# MCB-Wise-1510-v2_0_0.net
KiCad netlist of a schematic drawn in EAGLE
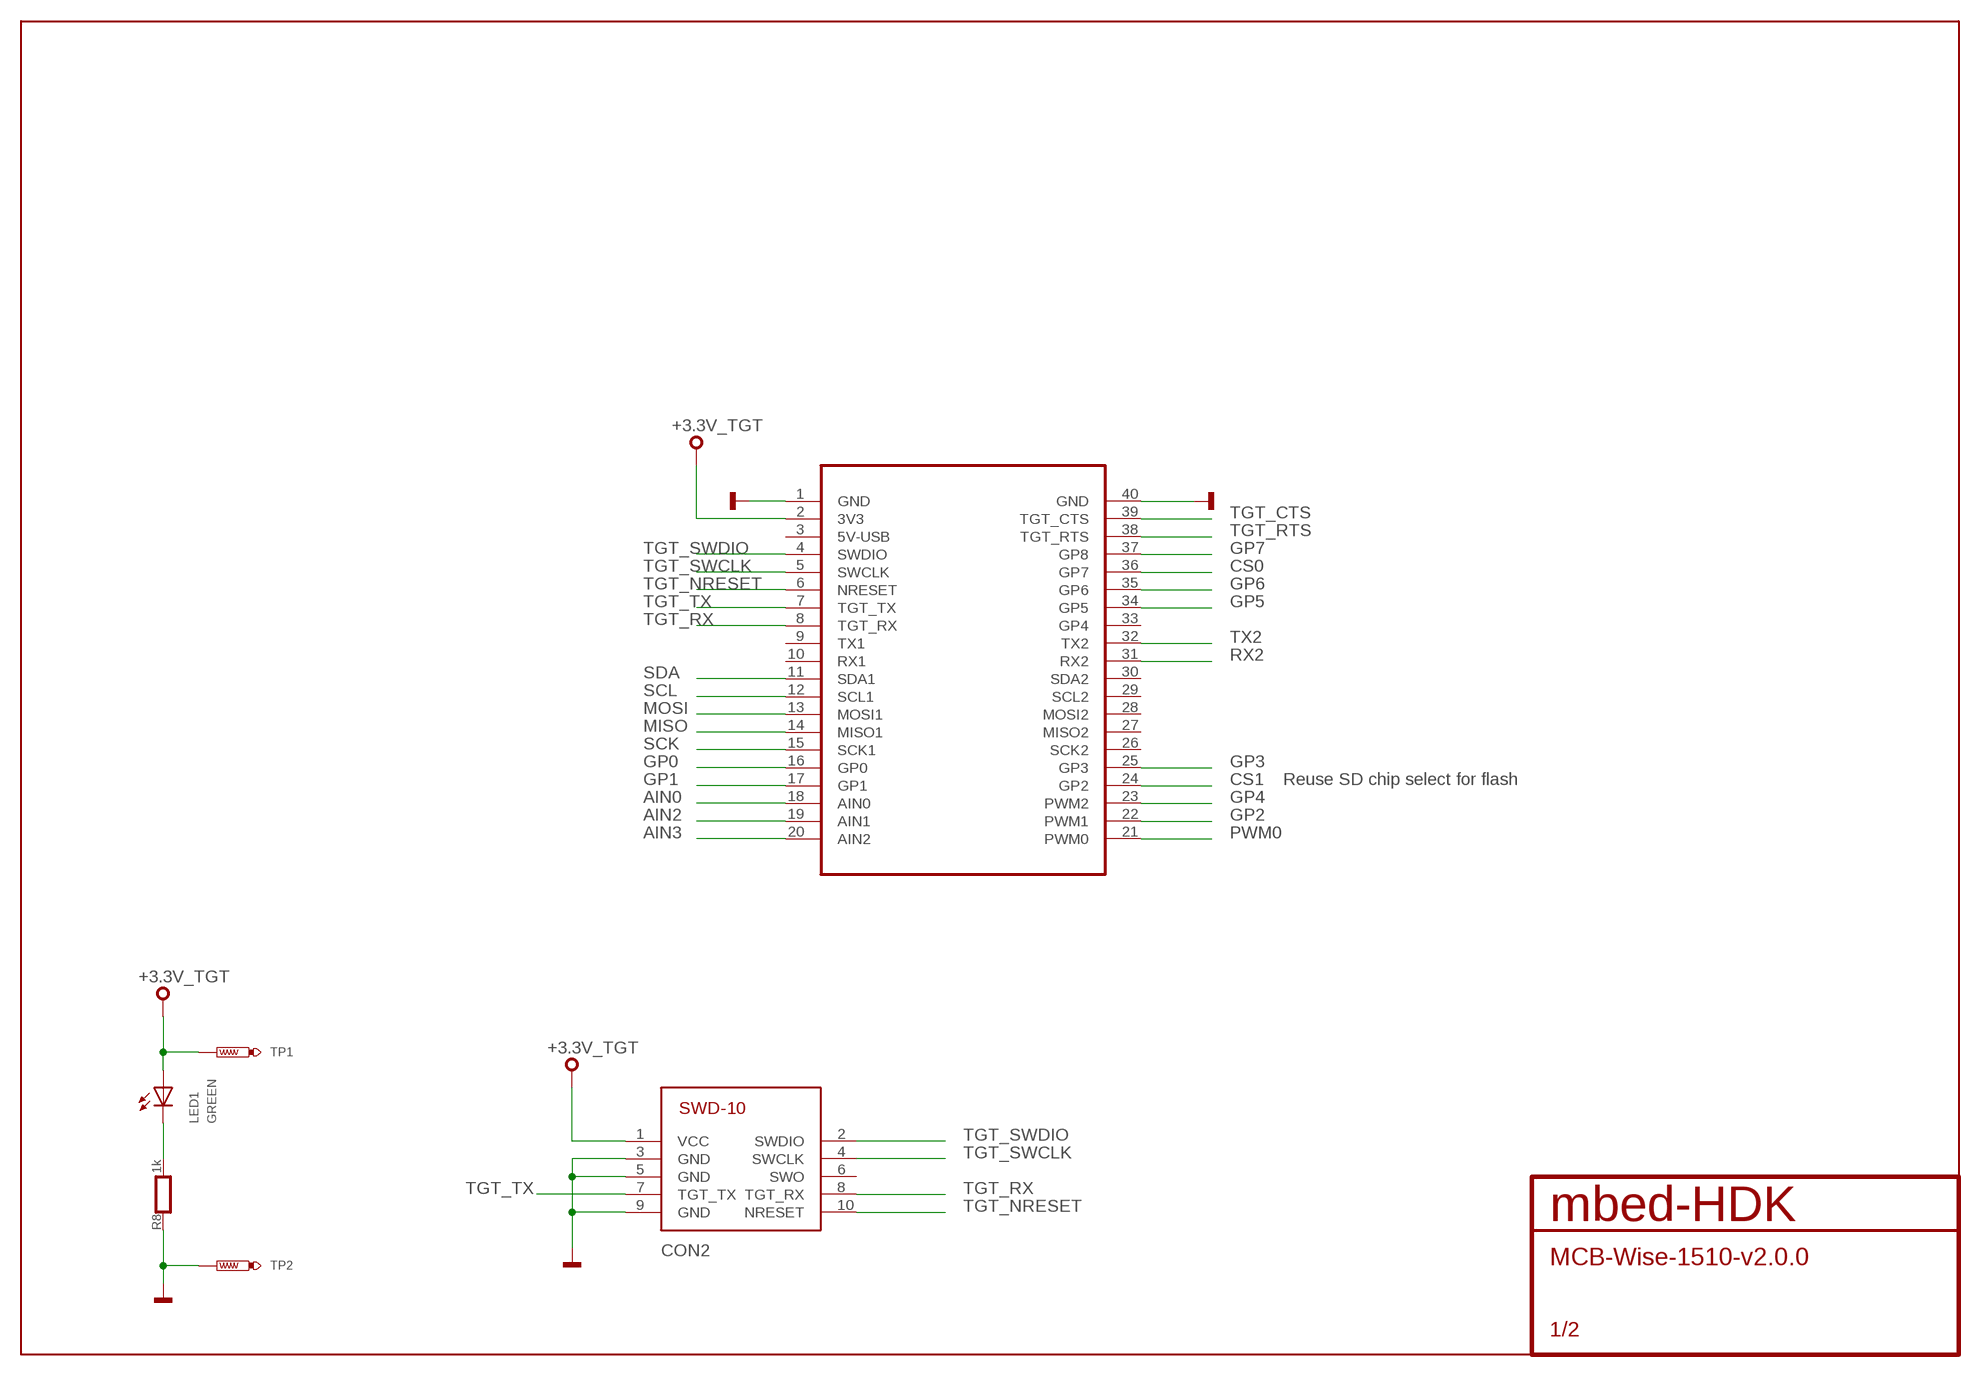
[diagram p0: schematic, sheet 1]
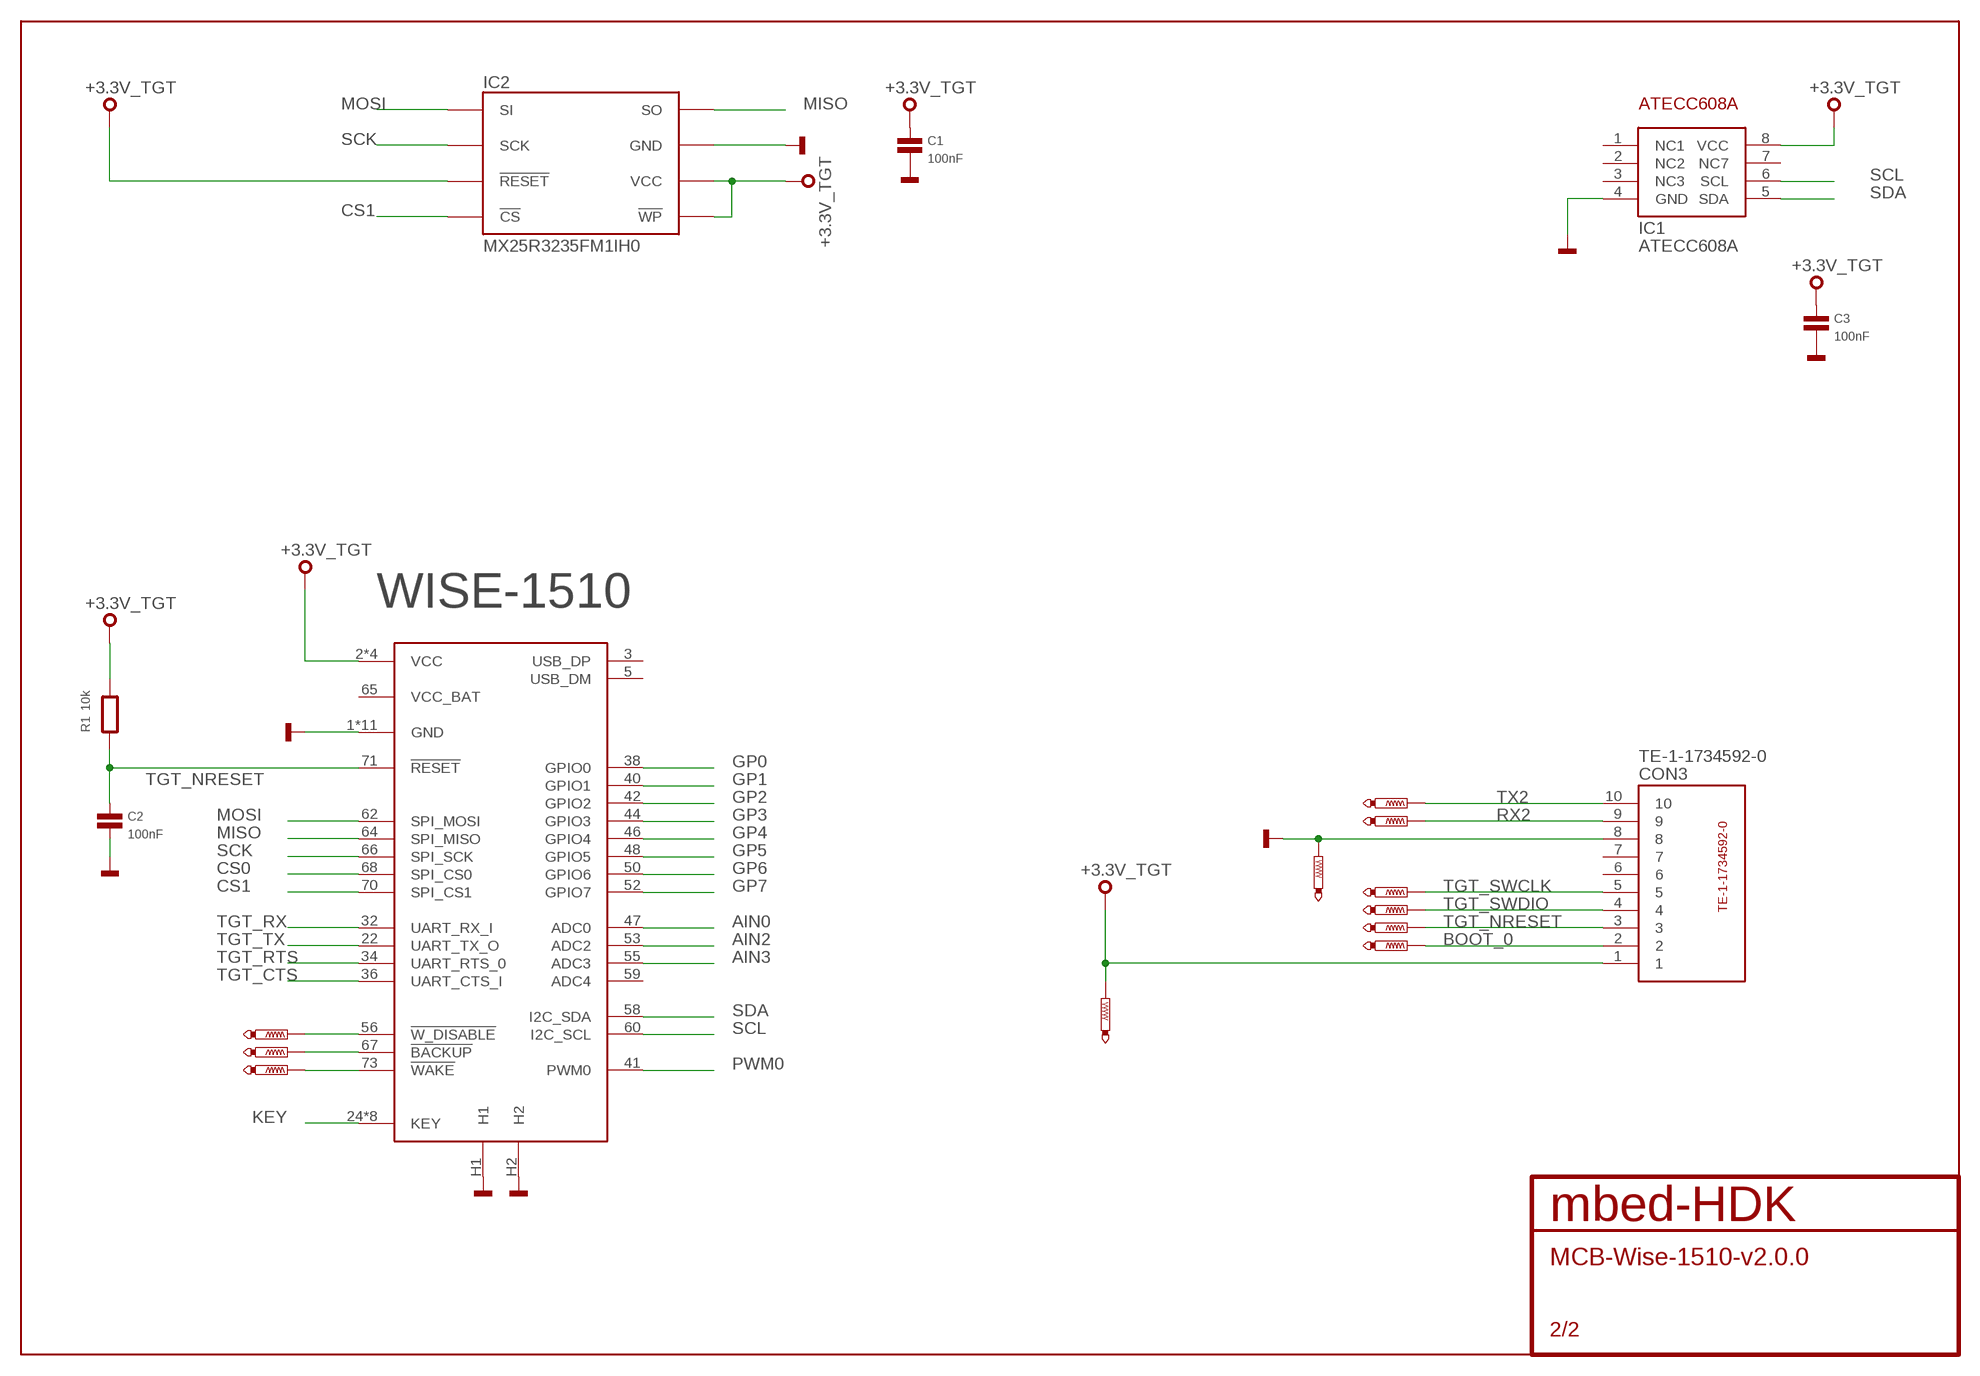
[diagram p1: schematic, sheet 2]

(export (version "E")
  (design (tool "Eeschema 10.0.6"))
  (components
    (comp (ref "C1")
      (value "100nF")
      (footprint "eagle-import:0603")
      (libsource (lib "eagle-import") (part "CAPACITOR0603"))
    )
    (comp (ref "C2")
      (value "100nF")
      (footprint "eagle-import:0603")
      (libsource (lib "eagle-import") (part "CAPACITOR0603"))
    )
    (comp (ref "C3")
      (value "100nF")
      (footprint "eagle-import:0603")
      (libsource (lib "eagle-import") (part "CAPACITOR0603"))
    )
    (comp (ref "CON1")
      (value "WISE-1510_E")
      (footprint "eagle-import:MDT420E02001")
      (libsource (lib "eagle-import") (part "WISE-1510_E"))
    )
    (comp (ref "CON3")
      (value "TE-1-1734592-0")
      (footprint "eagle-import:TE-1-1734592-0")
      (libsource (lib "eagle-import") (part "TE-1-1734592-0"))
    )
    (comp (ref "IC1")
      (value "ATECC608A")
      (footprint "eagle-import:SO8")
      (libsource (lib "eagle-import") (part "ATECC608A"))
    )
    (comp (ref "IC2")
      (value "MX25R3235FM1IH0")
      (footprint "eagle-import:SO8")
      (fields (field (name "MF") "Macronix"))
      (libsource (lib "eagle-import") (part "MX25R3235FM1IH0"))
    )
    (comp (ref "R1")
      (value "10k")
      (footprint "eagle-import:0603")
      (libsource (lib "eagle-import") (part "RESISTOR0603"))
    )
    (comp (ref "TP3")
      (value "PTR1TP08R")
      (footprint "eagle-import:TP08R")
      (libsource (lib "eagle-import") (part "PTR1TP08R"))
    )
    (comp (ref "TP4")
      (value "PTR1TP08R")
      (footprint "eagle-import:TP08R")
      (libsource (lib "eagle-import") (part "PTR1TP08R"))
    )
    (comp (ref "TP5")
      (value "PTR1TP08R")
      (footprint "eagle-import:TP08R")
      (libsource (lib "eagle-import") (part "PTR1TP08R"))
    )
    (comp (ref "TP6")
      (value "PTR1TP08R")
      (footprint "eagle-import:TP08R")
      (libsource (lib "eagle-import") (part "PTR1TP08R"))
    )
    (comp (ref "TP7")
      (value "PTR1TP08R")
      (footprint "eagle-import:TP08R")
      (libsource (lib "eagle-import") (part "PTR1TP08R"))
    )
    (comp (ref "TP8")
      (value "PTR1TP08R")
      (footprint "eagle-import:TP08R")
      (libsource (lib "eagle-import") (part "PTR1TP08R"))
    )
    (comp (ref "TP9")
      (value "PTR1B1,27")
      (footprint "eagle-import:B1,27")
      (libsource (lib "eagle-import") (part "PTR1B1,27"))
    )
    (comp (ref "TP10")
      (value "PTR1B1,27")
      (footprint "eagle-import:B1,27")
      (libsource (lib "eagle-import") (part "PTR1B1,27"))
    )
    (comp (ref "TP11")
      (value "PTR1B1,27")
      (footprint "eagle-import:B1,27")
      (libsource (lib "eagle-import") (part "PTR1B1,27"))
    )
    (comp (ref "TP12")
      (value "PTR1TP08R")
      (footprint "eagle-import:TP08R")
      (libsource (lib "eagle-import") (part "PTR1TP08R"))
    )
    (comp (ref "TP13")
      (value "PTR1TP08R")
      (footprint "eagle-import:TP08R")
      (libsource (lib "eagle-import") (part "PTR1TP08R"))
    )
    (comp (ref "CON2")
      (value "SWD-10/TC2050_SMD")
      (footprint "eagle-import:FTSH-105-02")
      (libsource (lib "eagle-import") (part "SWD-10/TC2050_SMD"))
    )
    (comp (ref "LED1")
      (value "GREEN")
      (footprint "eagle-import:CHIPLED_0603")
      (fields (field (name "MF") "Wurth Electronics Inc"))
      (libsource (lib "eagle-import") (part "SMD_LED0603"))
    )
    (comp (ref "R8")
      (value "1k")
      (footprint "eagle-import:0603")
      (libsource (lib "eagle-import") (part "RESISTOR0603"))
    )
    (comp (ref "TP1")
      (value "TEST-POINT-50R-PTH")
      (footprint "eagle-import:TP50-PTH")
      (libsource (lib "eagle-import") (part "TEST-POINT-50R-PTH"))
    )
    (comp (ref "TP2")
      (value "TEST-POINT-50R-PTH")
      (footprint "eagle-import:TP50-PTH")
      (libsource (lib "eagle-import") (part "TEST-POINT-50R-PTH"))
    )
    (comp (ref "U$1")
      (value "MODULE_DAUGHTER")
      (footprint "eagle-import:MODULE_DAUGHTER")
      (libsource (lib "eagle-import") (part "MODULE_DAUGHTER"))
    )
  )
  (nets
    (net (code "1") (name "+3.3V_TGT") (class "Default")
      (node (ref "C1") (pin "1") (pinfunction "P$1_1") (pintype "passive"))
      (node (ref "C3") (pin "1") (pinfunction "P$1_1") (pintype "passive"))
      (node (ref "CON1") (pin "2") (pinfunction "VCC_2") (pintype "bidirectional"))
      (node (ref "CON1") (pin "4") (pinfunction "VCC_4") (pintype "bidirectional"))
      (node (ref "CON1") (pin "72") (pinfunction "VCC_72") (pintype "bidirectional"))
      (node (ref "CON1") (pin "74") (pinfunction "VCC_74") (pintype "bidirectional"))
      (node (ref "CON2") (pin "1") (pinfunction "VCC_1") (pintype "bidirectional"))
      (node (ref "CON3") (pin "1") (pinfunction "1_1") (pintype "bidirectional"))
      (node (ref "IC1") (pin "8") (pinfunction "VCC_8") (pintype "bidirectional"))
      (node (ref "IC2") (pin "3") (pinfunction "~{WP}_3") (pintype "bidirectional"))
      (node (ref "IC2") (pin "7") (pinfunction "~{RESET}_7") (pintype "bidirectional"))
      (node (ref "IC2") (pin "8") (pinfunction "VCC_8") (pintype "bidirectional"))
      (node (ref "LED1") (pin "A") (pinfunction "A_A") (pintype "passive"))
      (node (ref "R1") (pin "2") (pinfunction "P$2_2") (pintype "passive"))
      (node (ref "TP1") (pin "TP") (pinfunction "TP_TP") (pintype "input"))
      (node (ref "TP12") (pin "TP") (pinfunction "TP_TP") (pintype "input"))
      (node (ref "U$1") (pin "2") (pinfunction "3V3_2") (pintype "bidirectional"))
    )
    (net (code "2") (name "AIN0") (class "Default")
      (node (ref "CON1") (pin "47") (pinfunction "ADC0_47") (pintype "bidirectional"))
      (node (ref "U$1") (pin "18") (pinfunction "AIN0_18") (pintype "bidirectional"))
    )
    (net (code "3") (name "AIN2") (class "Default")
      (node (ref "CON1") (pin "53") (pinfunction "ADC2_53") (pintype "bidirectional"))
      (node (ref "U$1") (pin "19") (pinfunction "AIN1_19") (pintype "bidirectional"))
    )
    (net (code "4") (name "AIN3") (class "Default")
      (node (ref "CON1") (pin "55") (pinfunction "ADC3_55") (pintype "bidirectional"))
      (node (ref "U$1") (pin "20") (pinfunction "AIN2_20") (pintype "bidirectional"))
    )
    (net (code "5") (name "BOOT_0") (class "Default")
      (node (ref "CON3") (pin "2") (pinfunction "2_2") (pintype "bidirectional"))
      (node (ref "TP8") (pin "TP") (pinfunction "TP_TP") (pintype "input"))
    )
    (net (code "6") (name "CS0") (class "Default")
      (node (ref "CON1") (pin "68") (pinfunction "SPI_CS0_68") (pintype "bidirectional"))
      (node (ref "U$1") (pin "36") (pinfunction "GP7_36") (pintype "bidirectional"))
    )
    (net (code "7") (name "CS1") (class "Default")
      (node (ref "CON1") (pin "70") (pinfunction "SPI_CS1_70") (pintype "bidirectional"))
      (node (ref "IC2") (pin "1") (pinfunction "~{CS}_1") (pintype "bidirectional"))
      (node (ref "U$1") (pin "24") (pinfunction "GP2_24") (pintype "bidirectional"))
    )
    (net (code "8") (name "GND") (class "Default")
      (node (ref "C1") (pin "2") (pinfunction "P$2_2") (pintype "passive"))
      (node (ref "C2") (pin "2") (pinfunction "P$2_2") (pintype "passive"))
      (node (ref "C3") (pin "2") (pinfunction "P$2_2") (pintype "passive"))
      (node (ref "CON1") (pin "1") (pinfunction "GND_1") (pintype "bidirectional"))
      (node (ref "CON1") (pin "18") (pinfunction "GND_18") (pintype "bidirectional"))
      (node (ref "CON1") (pin "33") (pinfunction "GND_33") (pintype "bidirectional"))
      (node (ref "CON1") (pin "39") (pinfunction "GND_39") (pintype "bidirectional"))
      (node (ref "CON1") (pin "45") (pinfunction "GND_45") (pintype "bidirectional"))
      (node (ref "CON1") (pin "51") (pinfunction "GND_51") (pintype "bidirectional"))
      (node (ref "CON1") (pin "57") (pinfunction "GND_57") (pintype "bidirectional"))
      (node (ref "CON1") (pin "63") (pinfunction "GND_63") (pintype "bidirectional"))
      (node (ref "CON1") (pin "69") (pinfunction "GND_69") (pintype "bidirectional"))
      (node (ref "CON1") (pin "7") (pinfunction "GND_7") (pintype "bidirectional"))
      (node (ref "CON1") (pin "75") (pinfunction "GND_75") (pintype "bidirectional"))
      (node (ref "CON1") (pin "H1") (pinfunction "H1_H1") (pintype "bidirectional"))
      (node (ref "CON1") (pin "H2") (pinfunction "H2_H2") (pintype "bidirectional"))
      (node (ref "CON2") (pin "3") (pinfunction "GND_3") (pintype "bidirectional"))
      (node (ref "CON2") (pin "5") (pinfunction "GND_5") (pintype "bidirectional"))
      (node (ref "CON2") (pin "9") (pinfunction "GND_9") (pintype "bidirectional"))
      (node (ref "CON3") (pin "8") (pinfunction "8_8") (pintype "bidirectional"))
      (node (ref "IC1") (pin "4") (pinfunction "GND_4") (pintype "bidirectional"))
      (node (ref "IC2") (pin "4") (pinfunction "GND_4") (pintype "bidirectional"))
      (node (ref "R8") (pin "1") (pinfunction "P$1_1") (pintype "passive"))
      (node (ref "TP13") (pin "TP") (pinfunction "TP_TP") (pintype "input"))
      (node (ref "TP2") (pin "TP") (pinfunction "TP_TP") (pintype "input"))
      (node (ref "U$1") (pin "1") (pinfunction "GND_1") (pintype "bidirectional"))
      (node (ref "U$1") (pin "40") (pinfunction "GND_40") (pintype "bidirectional"))
    )
    (net (code "9") (name "GP0") (class "Default")
      (node (ref "CON1") (pin "38") (pinfunction "GPIO0_38") (pintype "bidirectional"))
      (node (ref "U$1") (pin "16") (pinfunction "GP0_16") (pintype "bidirectional"))
    )
    (net (code "10") (name "GP1") (class "Default")
      (node (ref "CON1") (pin "40") (pinfunction "GPIO1_40") (pintype "bidirectional"))
      (node (ref "U$1") (pin "17") (pinfunction "GP1_17") (pintype "bidirectional"))
    )
    (net (code "11") (name "GP2") (class "Default")
      (node (ref "CON1") (pin "42") (pinfunction "GPIO2_42") (pintype "bidirectional"))
      (node (ref "U$1") (pin "22") (pinfunction "PWM1_22") (pintype "bidirectional"))
    )
    (net (code "12") (name "GP3") (class "Default")
      (node (ref "CON1") (pin "44") (pinfunction "GPIO3_44") (pintype "bidirectional"))
      (node (ref "U$1") (pin "25") (pinfunction "GP3_25") (pintype "bidirectional"))
    )
    (net (code "13") (name "GP4") (class "Default")
      (node (ref "CON1") (pin "46") (pinfunction "GPIO4_46") (pintype "bidirectional"))
      (node (ref "U$1") (pin "23") (pinfunction "PWM2_23") (pintype "bidirectional"))
    )
    (net (code "14") (name "GP5") (class "Default")
      (node (ref "CON1") (pin "48") (pinfunction "GPIO5_48") (pintype "bidirectional"))
      (node (ref "U$1") (pin "34") (pinfunction "GP5_34") (pintype "bidirectional"))
    )
    (net (code "15") (name "GP6") (class "Default")
      (node (ref "CON1") (pin "50") (pinfunction "GPIO6_50") (pintype "bidirectional"))
      (node (ref "U$1") (pin "35") (pinfunction "GP6_35") (pintype "bidirectional"))
    )
    (net (code "16") (name "GP7") (class "Default")
      (node (ref "CON1") (pin "52") (pinfunction "GPIO7_52") (pintype "bidirectional"))
      (node (ref "U$1") (pin "37") (pinfunction "GP8_37") (pintype "bidirectional"))
    )
    (net (code "17") (name "KEY") (class "Default")
      (node (ref "CON1") (pin "24") (pinfunction "KEY_24") (pintype "bidirectional"))
      (node (ref "CON1") (pin "25") (pinfunction "KEY_25") (pintype "bidirectional"))
      (node (ref "CON1") (pin "26") (pinfunction "KEY_26") (pintype "bidirectional"))
      (node (ref "CON1") (pin "27") (pinfunction "KEY_27") (pintype "bidirectional"))
      (node (ref "CON1") (pin "28") (pinfunction "KEY_28") (pintype "bidirectional"))
      (node (ref "CON1") (pin "29") (pinfunction "KEY_29") (pintype "bidirectional"))
      (node (ref "CON1") (pin "30") (pinfunction "KEY_30") (pintype "bidirectional"))
      (node (ref "CON1") (pin "31") (pinfunction "KEY_31") (pintype "bidirectional"))
    )
    (net (code "18") (name "MISO") (class "Default")
      (node (ref "CON1") (pin "64") (pinfunction "SPI_MISO_64") (pintype "bidirectional"))
      (node (ref "IC2") (pin "2") (pinfunction "SO_2") (pintype "bidirectional"))
      (node (ref "U$1") (pin "14") (pinfunction "MISO1_14") (pintype "bidirectional"))
    )
    (net (code "19") (name "MOSI") (class "Default")
      (node (ref "CON1") (pin "62") (pinfunction "SPI_MOSI_62") (pintype "bidirectional"))
      (node (ref "IC2") (pin "5") (pinfunction "SI_5") (pintype "bidirectional"))
      (node (ref "U$1") (pin "13") (pinfunction "MOSI1_13") (pintype "bidirectional"))
    )
    (net (code "20") (name "Net-(CON1-~{BACKUP})") (class "Default")
      (node (ref "CON1") (pin "67") (pinfunction "~{BACKUP}_67") (pintype "bidirectional"))
      (node (ref "TP10") (pin "TP") (pinfunction "TP_TP") (pintype "input"))
    )
    (net (code "21") (name "Net-(CON1-~{WAKE})") (class "Default")
      (node (ref "CON1") (pin "73") (pinfunction "~{WAKE}_73") (pintype "bidirectional"))
      (node (ref "TP11") (pin "TP") (pinfunction "TP_TP") (pintype "input"))
    )
    (net (code "22") (name "Net-(CON1-~{W_DISABLE})") (class "Default")
      (node (ref "CON1") (pin "56") (pinfunction "~{W_DISABLE}_56") (pintype "bidirectional"))
      (node (ref "TP9") (pin "TP") (pinfunction "TP_TP") (pintype "input"))
    )
    (net (code "23") (name "Net-(R8-P$2)") (class "Default")
      (node (ref "LED1") (pin "C") (pinfunction "C_C") (pintype "passive"))
      (node (ref "R8") (pin "2") (pinfunction "P$2_2") (pintype "passive"))
    )
    (net (code "24") (name "PWM0") (class "Default")
      (node (ref "CON1") (pin "41") (pinfunction "PWM0_41") (pintype "bidirectional"))
      (node (ref "U$1") (pin "21") (pinfunction "PWM0_21") (pintype "bidirectional"))
    )
    (net (code "25") (name "RX2") (class "Default")
      (node (ref "CON3") (pin "9") (pinfunction "9_9") (pintype "bidirectional"))
      (node (ref "TP6") (pin "TP") (pinfunction "TP_TP") (pintype "input"))
      (node (ref "U$1") (pin "31") (pinfunction "RX2_31") (pintype "bidirectional"))
    )
    (net (code "26") (name "SCK") (class "Default")
      (node (ref "CON1") (pin "66") (pinfunction "SPI_SCK_66") (pintype "bidirectional"))
      (node (ref "IC2") (pin "6") (pinfunction "SCK_6") (pintype "bidirectional"))
      (node (ref "U$1") (pin "15") (pinfunction "SCK1_15") (pintype "bidirectional"))
    )
    (net (code "27") (name "SCL") (class "Default")
      (node (ref "CON1") (pin "60") (pinfunction "I2C_SCL_60") (pintype "bidirectional"))
      (node (ref "IC1") (pin "6") (pinfunction "SCL_6") (pintype "bidirectional"))
      (node (ref "U$1") (pin "12") (pinfunction "SCL1_12") (pintype "bidirectional"))
    )
    (net (code "28") (name "SDA") (class "Default")
      (node (ref "CON1") (pin "58") (pinfunction "I2C_SDA_58") (pintype "bidirectional"))
      (node (ref "IC1") (pin "5") (pinfunction "SDA_5") (pintype "bidirectional"))
      (node (ref "U$1") (pin "11") (pinfunction "SDA1_11") (pintype "bidirectional"))
    )
    (net (code "29") (name "TGT_CTS") (class "Default")
      (node (ref "CON1") (pin "36") (pinfunction "UART_CTS_I_36") (pintype "bidirectional"))
      (node (ref "U$1") (pin "39") (pinfunction "TGT_CTS_39") (pintype "bidirectional"))
    )
    (net (code "30") (name "TGT_NRESET") (class "Default")
      (node (ref "C2") (pin "1") (pinfunction "P$1_1") (pintype "passive"))
      (node (ref "CON1") (pin "71") (pinfunction "~{RESET}_71") (pintype "bidirectional"))
      (node (ref "CON2") (pin "10") (pinfunction "NRESET_10") (pintype "bidirectional"))
      (node (ref "CON3") (pin "3") (pinfunction "3_3") (pintype "bidirectional"))
      (node (ref "R1") (pin "1") (pinfunction "P$1_1") (pintype "passive"))
      (node (ref "TP5") (pin "TP") (pinfunction "TP_TP") (pintype "input"))
      (node (ref "U$1") (pin "6") (pinfunction "NRESET_6") (pintype "bidirectional"))
    )
    (net (code "31") (name "TGT_RTS") (class "Default")
      (node (ref "CON1") (pin "34") (pinfunction "UART_RTS_0_34") (pintype "bidirectional"))
      (node (ref "U$1") (pin "38") (pinfunction "TGT_RTS_38") (pintype "bidirectional"))
    )
    (net (code "32") (name "TGT_RX") (class "Default")
      (node (ref "CON1") (pin "32") (pinfunction "UART_RX_I_32") (pintype "bidirectional"))
      (node (ref "CON2") (pin "8") (pinfunction "TGT_RX_8") (pintype "bidirectional"))
      (node (ref "U$1") (pin "8") (pinfunction "TGT_RX_8") (pintype "bidirectional"))
    )
    (net (code "33") (name "TGT_SWCLK") (class "Default")
      (node (ref "CON2") (pin "4") (pinfunction "SWCLK_4") (pintype "bidirectional"))
      (node (ref "CON3") (pin "5") (pinfunction "5_5") (pintype "bidirectional"))
      (node (ref "TP3") (pin "TP") (pinfunction "TP_TP") (pintype "input"))
      (node (ref "U$1") (pin "5") (pinfunction "SWCLK_5") (pintype "bidirectional"))
    )
    (net (code "34") (name "TGT_SWDIO") (class "Default")
      (node (ref "CON2") (pin "2") (pinfunction "SWDIO_2") (pintype "bidirectional"))
      (node (ref "CON3") (pin "4") (pinfunction "4_4") (pintype "bidirectional"))
      (node (ref "TP4") (pin "TP") (pinfunction "TP_TP") (pintype "input"))
      (node (ref "U$1") (pin "4") (pinfunction "SWDIO_4") (pintype "bidirectional"))
    )
    (net (code "35") (name "TGT_TX") (class "Default")
      (node (ref "CON1") (pin "22") (pinfunction "UART_TX_O_22") (pintype "bidirectional"))
      (node (ref "CON2") (pin "7") (pinfunction "TGT_TX_7") (pintype "bidirectional"))
      (node (ref "U$1") (pin "7") (pinfunction "TGT_TX_7") (pintype "bidirectional"))
    )
    (net (code "36") (name "TX2") (class "Default")
      (node (ref "CON3") (pin "10") (pinfunction "10_10") (pintype "bidirectional"))
      (node (ref "TP7") (pin "TP") (pinfunction "TP_TP") (pintype "input"))
      (node (ref "U$1") (pin "32") (pinfunction "TX2_32") (pintype "bidirectional"))
    )
    (net (code "37") (name "unconnected-(CON1-ADC4-Pad59)") (class "Default")
      (node (ref "CON1") (pin "59") (pinfunction "ADC4_59") (pintype "bidirectional"))
    )
    (net (code "38") (name "unconnected-(CON1-USB_DM-Pad5)") (class "Default")
      (node (ref "CON1") (pin "5") (pinfunction "USB_DM_5") (pintype "bidirectional"))
    )
    (net (code "39") (name "unconnected-(CON1-USB_DP-Pad3)") (class "Default")
      (node (ref "CON1") (pin "3") (pinfunction "USB_DP_3") (pintype "bidirectional"))
    )
    (net (code "40") (name "unconnected-(CON1-VCC_BAT-Pad65)") (class "Default")
      (node (ref "CON1") (pin "65") (pinfunction "VCC_BAT_65") (pintype "bidirectional"))
    )
    (net (code "41") (name "unconnected-(CON2-SWO-Pad6)") (class "Default")
      (node (ref "CON2") (pin "6") (pinfunction "SWO_6") (pintype "bidirectional"))
    )
    (net (code "42") (name "unconnected-(CON3-Pad6)") (class "Default")
      (node (ref "CON3") (pin "6") (pinfunction "6_6") (pintype "bidirectional"))
    )
    (net (code "43") (name "unconnected-(CON3-Pad7)") (class "Default")
      (node (ref "CON3") (pin "7") (pinfunction "7_7") (pintype "bidirectional"))
    )
    (net (code "44") (name "unconnected-(IC1-NC1-Pad1)") (class "Default")
      (node (ref "IC1") (pin "1") (pinfunction "NC1_1") (pintype "bidirectional"))
    )
    (net (code "45") (name "unconnected-(IC1-NC2-Pad2)") (class "Default")
      (node (ref "IC1") (pin "2") (pinfunction "NC2_2") (pintype "bidirectional"))
    )
    (net (code "46") (name "unconnected-(IC1-NC3-Pad3)") (class "Default")
      (node (ref "IC1") (pin "3") (pinfunction "NC3_3") (pintype "bidirectional"))
    )
    (net (code "47") (name "unconnected-(IC1-NC7-Pad7)") (class "Default")
      (node (ref "IC1") (pin "7") (pinfunction "NC7_7") (pintype "bidirectional"))
    )
    (net (code "48") (name "unconnected-(U$1-5V-USB-Pad3)") (class "Default")
      (node (ref "U$1") (pin "3") (pinfunction "5V-USB_3") (pintype "bidirectional"))
    )
    (net (code "49") (name "unconnected-(U$1-GP4-Pad33)") (class "Default")
      (node (ref "U$1") (pin "33") (pinfunction "GP4_33") (pintype "bidirectional"))
    )
    (net (code "50") (name "unconnected-(U$1-MISO2-Pad27)") (class "Default")
      (node (ref "U$1") (pin "27") (pinfunction "MISO2_27") (pintype "bidirectional"))
    )
    (net (code "51") (name "unconnected-(U$1-MOSI2-Pad28)") (class "Default")
      (node (ref "U$1") (pin "28") (pinfunction "MOSI2_28") (pintype "bidirectional"))
    )
    (net (code "52") (name "unconnected-(U$1-RX1-Pad10)") (class "Default")
      (node (ref "U$1") (pin "10") (pinfunction "RX1_10") (pintype "bidirectional"))
    )
    (net (code "53") (name "unconnected-(U$1-SCK2-Pad26)") (class "Default")
      (node (ref "U$1") (pin "26") (pinfunction "SCK2_26") (pintype "bidirectional"))
    )
    (net (code "54") (name "unconnected-(U$1-SCL2-Pad29)") (class "Default")
      (node (ref "U$1") (pin "29") (pinfunction "SCL2_29") (pintype "bidirectional"))
    )
    (net (code "55") (name "unconnected-(U$1-SDA2-Pad30)") (class "Default")
      (node (ref "U$1") (pin "30") (pinfunction "SDA2_30") (pintype "bidirectional"))
    )
    (net (code "56") (name "unconnected-(U$1-TX1-Pad9)") (class "Default")
      (node (ref "U$1") (pin "9") (pinfunction "TX1_9") (pintype "bidirectional"))
    )
  )
)
